# BV100011_ControlAI.net
KiCad netlist of a schematic drawn in Altium Designer
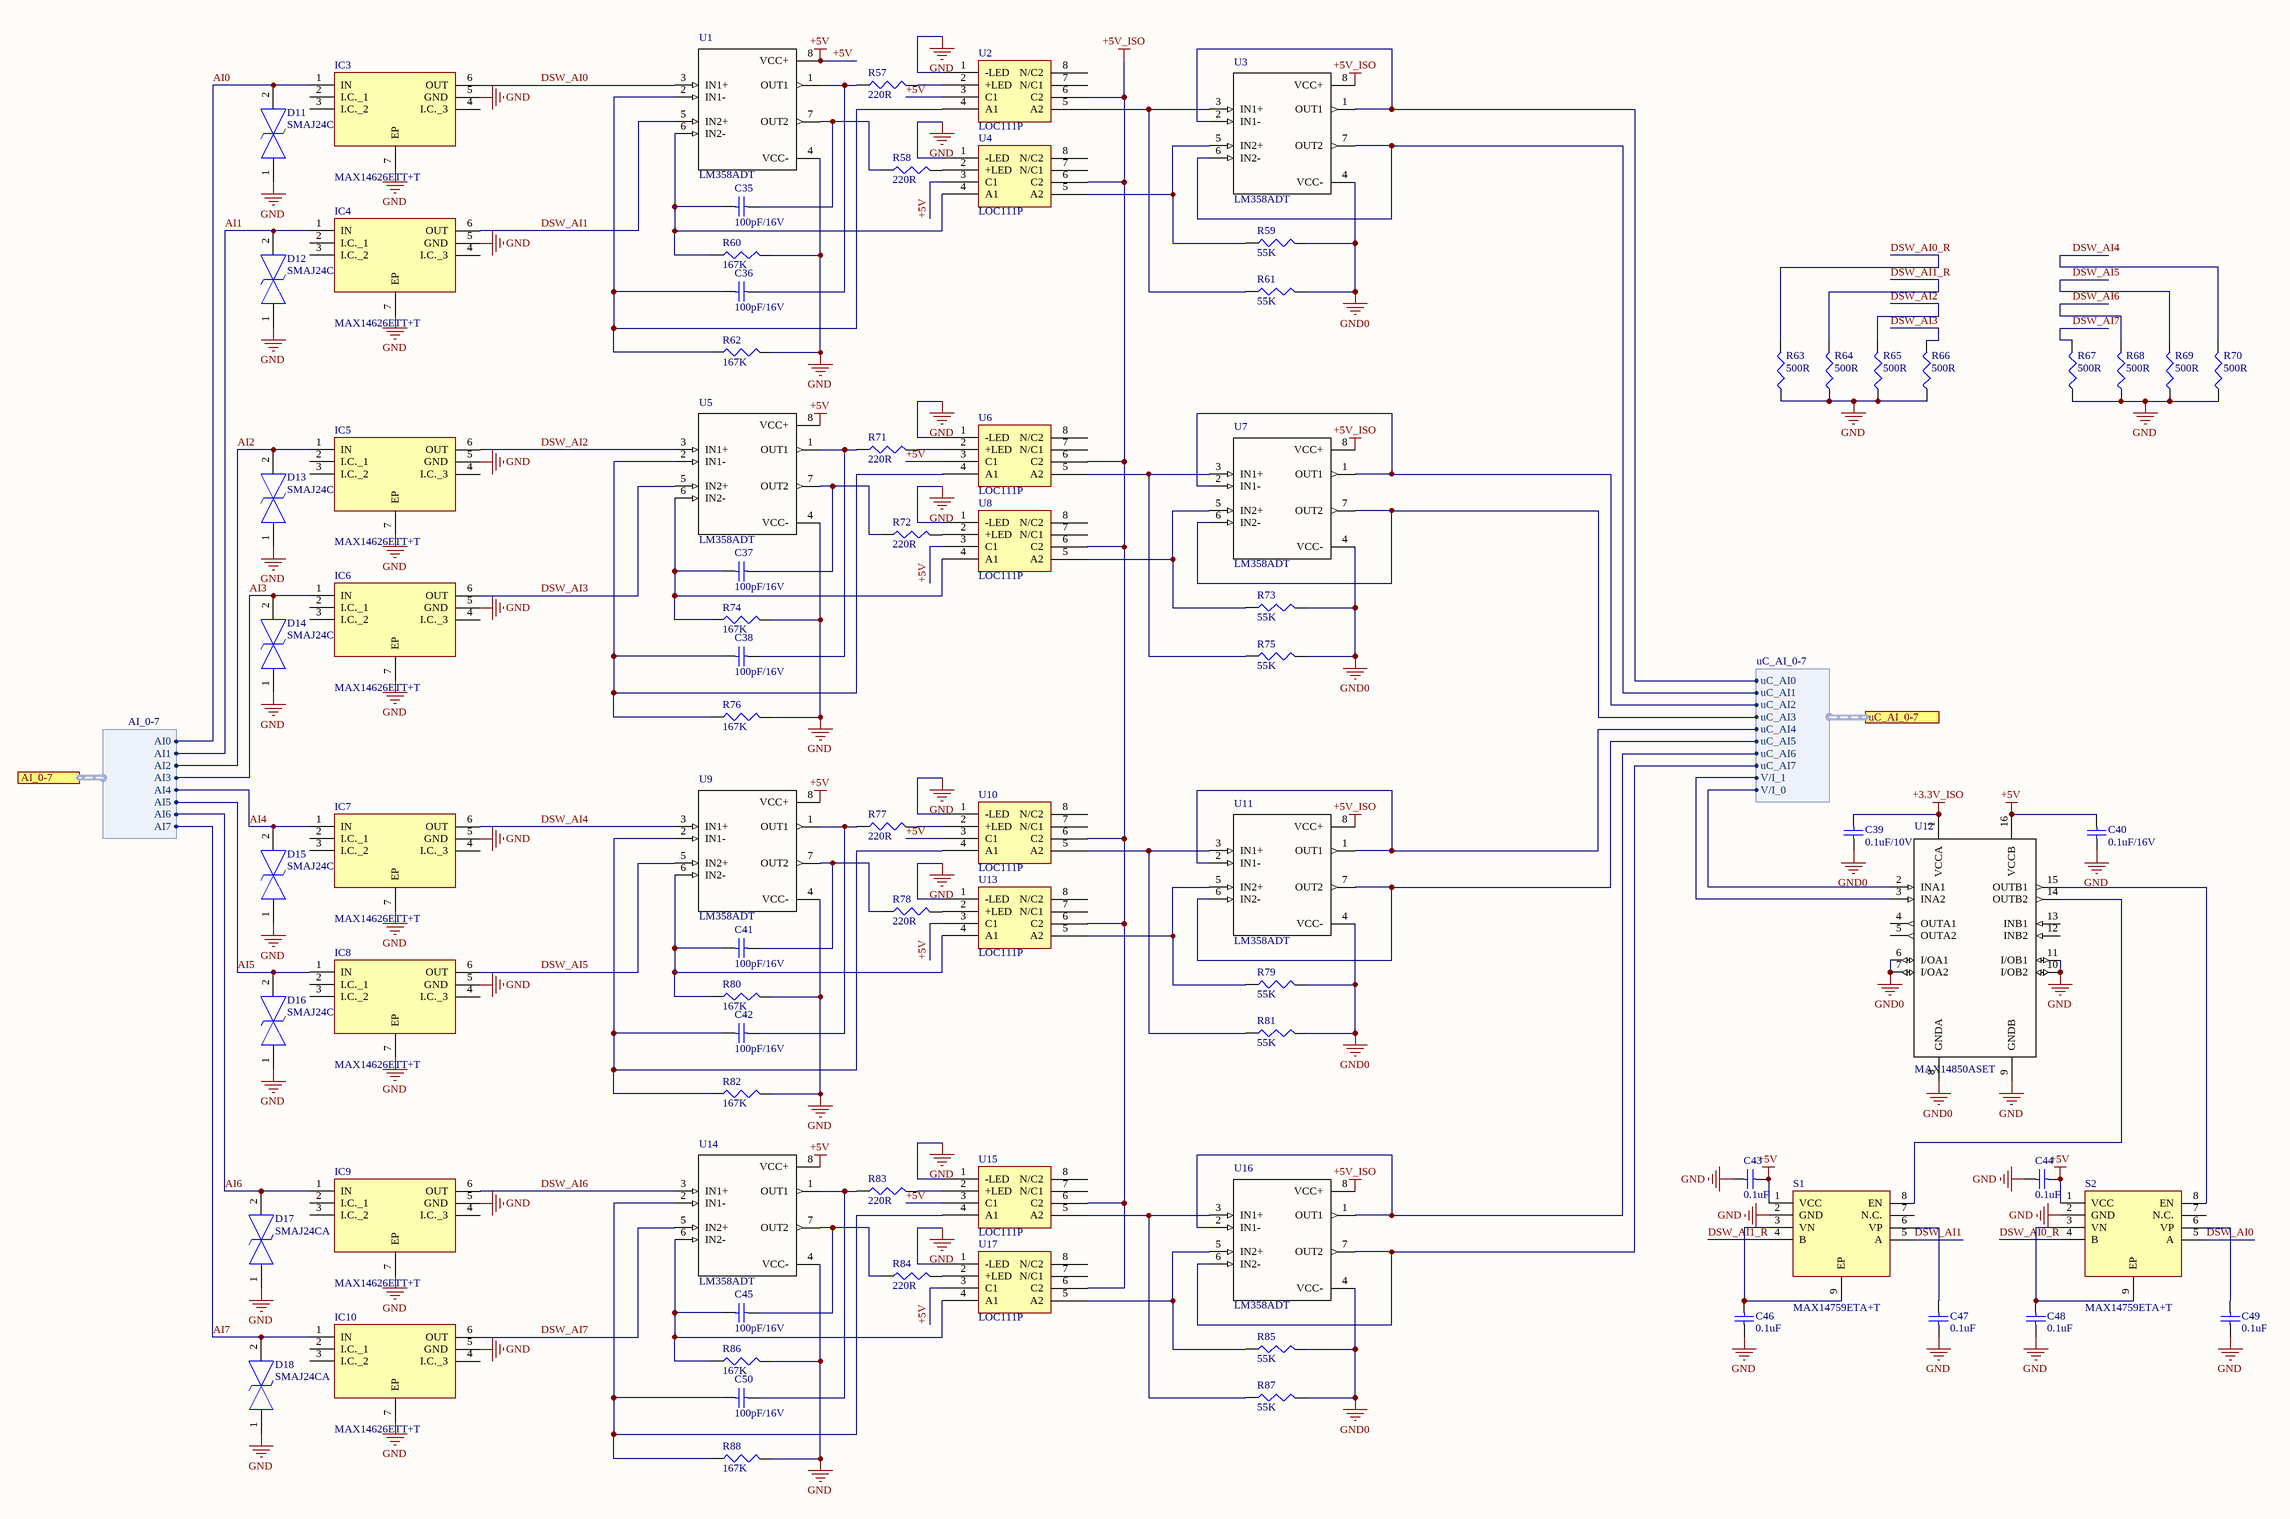
[diagram p0: BV100011_ControlAI.SchDoc]

(export (version "E")
  (design (tool "Eeschema 10.0.6"))
  (components
    (comp (ref "C35")
      (value "100pF/16V")
      (footprint "C1206")
      (description "Capacitor (Semiconductor SIM Model)")
      (fields (field (name "PUBLISHER") "Altium Limited"))
      (libsource (lib "Miscellaneous Devices") (part "Cap Semi"))
    )
    (comp (ref "C36")
      (value "100pF/16V")
      (footprint "C1206")
      (description "Capacitor (Semiconductor SIM Model)")
      (fields (field (name "PUBLISHER") "Altium Limited"))
      (libsource (lib "Miscellaneous Devices") (part "Cap Semi"))
    )
    (comp (ref "C37")
      (value "100pF/16V")
      (footprint "C1206")
      (description "Capacitor (Semiconductor SIM Model)")
      (fields (field (name "PUBLISHER") "Altium Limited"))
      (libsource (lib "Miscellaneous Devices") (part "Cap Semi"))
    )
    (comp (ref "C38")
      (value "100pF/16V")
      (footprint "C1206")
      (description "Capacitor (Semiconductor SIM Model)")
      (fields (field (name "PUBLISHER") "Altium Limited"))
      (libsource (lib "Miscellaneous Devices") (part "Cap Semi"))
    )
    (comp (ref "C39")
      (value "0.1uF/10V")
      (footprint "C1206")
      (description "Capacitor (Semiconductor SIM Model)")
      (fields (field (name "PUBLISHER") "Altium Limited"))
      (libsource (lib "Miscellaneous Devices") (part "Cap Semi"))
    )
    (comp (ref "C40")
      (value "0.1uF/16V")
      (footprint "C1206")
      (description "Capacitor (Semiconductor SIM Model)")
      (fields (field (name "PUBLISHER") "Altium Limited"))
      (libsource (lib "Miscellaneous Devices") (part "Cap Semi"))
    )
    (comp (ref "C41")
      (value "100pF/16V")
      (footprint "C1206")
      (description "Capacitor (Semiconductor SIM Model)")
      (fields (field (name "PUBLISHER") "Altium Limited"))
      (libsource (lib "Miscellaneous Devices") (part "Cap Semi"))
    )
    (comp (ref "C42")
      (value "100pF/16V")
      (footprint "C1206")
      (description "Capacitor (Semiconductor SIM Model)")
      (fields (field (name "PUBLISHER") "Altium Limited"))
      (libsource (lib "Miscellaneous Devices") (part "Cap Semi"))
    )
    (comp (ref "C43")
      (value "0.1uF")
      (footprint "C1206")
      (description "Capacitor (Semiconductor SIM Model)")
      (fields (field (name "PUBLISHER") "Altium Limited"))
      (libsource (lib "Miscellaneous Devices") (part "Cap Semi"))
    )
    (comp (ref "C44")
      (value "0.1uF")
      (footprint "C1206")
      (description "Capacitor (Semiconductor SIM Model)")
      (fields (field (name "PUBLISHER") "Altium Limited"))
      (libsource (lib "Miscellaneous Devices") (part "Cap Semi"))
    )
    (comp (ref "C45")
      (value "100pF/16V")
      (footprint "C1206")
      (description "Capacitor (Semiconductor SIM Model)")
      (fields (field (name "PUBLISHER") "Altium Limited"))
      (libsource (lib "Miscellaneous Devices") (part "Cap Semi"))
    )
    (comp (ref "C46")
      (value "0.1uF")
      (footprint "C1206")
      (description "Capacitor (Semiconductor SIM Model)")
      (fields (field (name "PUBLISHER") "Altium Limited"))
      (libsource (lib "Miscellaneous Devices") (part "Cap Semi"))
    )
    (comp (ref "C47")
      (value "0.1uF")
      (footprint "C1206")
      (description "Capacitor (Semiconductor SIM Model)")
      (fields (field (name "PUBLISHER") "Altium Limited"))
      (libsource (lib "Miscellaneous Devices") (part "Cap Semi"))
    )
    (comp (ref "C48")
      (value "0.1uF")
      (footprint "C1206")
      (description "Capacitor (Semiconductor SIM Model)")
      (fields (field (name "PUBLISHER") "Altium Limited"))
      (libsource (lib "Miscellaneous Devices") (part "Cap Semi"))
    )
    (comp (ref "C49")
      (value "0.1uF")
      (footprint "C1206")
      (description "Capacitor (Semiconductor SIM Model)")
      (fields (field (name "PUBLISHER") "Altium Limited"))
      (libsource (lib "Miscellaneous Devices") (part "Cap Semi"))
    )
    (comp (ref "C50")
      (value "100pF/16V")
      (footprint "C1206")
      (description "Capacitor (Semiconductor SIM Model)")
      (fields (field (name "PUBLISHER") "Altium Limited"))
      (libsource (lib "Miscellaneous Devices") (part "Cap Semi"))
    )
    (comp (ref "D11")
      (value "SMAJ24CA")
      (footprint "DIONM5026X229N")
      (description "TVS Diode (Bi-directional)")
      (fields (field (name "MOUSER PART NUMBER") "576-SMAJ24CA") (field (name "RS PART NUMBER") "1719613P"))
      (libsource (lib "SMAJ24CA") (part "SMAJ24CA"))
    )
    (comp (ref "D12")
      (value "SMAJ24CA")
      (footprint "DIONM5026X229N")
      (description "TVS Diode (Bi-directional)")
      (fields (field (name "MOUSER PART NUMBER") "576-SMAJ24CA") (field (name "RS PART NUMBER") "1719613P"))
      (libsource (lib "SMAJ24CA") (part "SMAJ24CA"))
    )
    (comp (ref "D13")
      (value "SMAJ24CA")
      (footprint "DIONM5026X229N")
      (description "TVS Diode (Bi-directional)")
      (fields (field (name "MOUSER PART NUMBER") "576-SMAJ24CA") (field (name "RS PART NUMBER") "1719613P"))
      (libsource (lib "SMAJ24CA") (part "SMAJ24CA"))
    )
    (comp (ref "D14")
      (value "SMAJ24CA")
      (footprint "DIONM5026X229N")
      (description "TVS Diode (Bi-directional)")
      (fields (field (name "MOUSER PART NUMBER") "576-SMAJ24CA") (field (name "RS PART NUMBER") "1719613P"))
      (libsource (lib "SMAJ24CA") (part "SMAJ24CA"))
    )
    (comp (ref "D15")
      (value "SMAJ24CA")
      (footprint "DIONM5026X229N")
      (description "TVS Diode (Bi-directional)")
      (fields (field (name "MOUSER PART NUMBER") "576-SMAJ24CA") (field (name "RS PART NUMBER") "1719613P"))
      (libsource (lib "SMAJ24CA") (part "SMAJ24CA"))
    )
    (comp (ref "D16")
      (value "SMAJ24CA")
      (footprint "DIONM5026X229N")
      (description "TVS Diode (Bi-directional)")
      (fields (field (name "MOUSER PART NUMBER") "576-SMAJ24CA") (field (name "RS PART NUMBER") "1719613P"))
      (libsource (lib "SMAJ24CA") (part "SMAJ24CA"))
    )
    (comp (ref "D17")
      (value "SMAJ24CA")
      (footprint "DIONM5026X229N")
      (description "TVS Diode (Bi-directional)")
      (fields (field (name "MOUSER PART NUMBER") "576-SMAJ24CA") (field (name "RS PART NUMBER") "1719613P"))
      (libsource (lib "SMAJ24CA") (part "SMAJ24CA"))
    )
    (comp (ref "D18")
      (value "SMAJ24CA")
      (footprint "DIONM5026X229N")
      (description "TVS Diode (Bi-directional)")
      (fields (field (name "MOUSER PART NUMBER") "576-SMAJ24CA") (field (name "RS PART NUMBER") "1719613P"))
      (libsource (lib "SMAJ24CA") (part "SMAJ24CA"))
    )
    (comp (ref "IC3")
      (value "MAX14626ETT+T")
      (footprint "SamacSys:SON95P300X300X80-7N")
      (description "Integrated Circuit")
      (fields (field (name "MOUSER PART NUMBER") "700-MAX14626ETT+T"))
      (libsource (lib "*") (part "MAX14626ETT+T"))
    )
    (comp (ref "IC4")
      (value "MAX14626ETT+T")
      (footprint "SamacSys:SON95P300X300X80-7N")
      (description "Integrated Circuit")
      (fields (field (name "MOUSER PART NUMBER") "700-MAX14626ETT+T"))
      (libsource (lib "*") (part "MAX14626ETT+T"))
    )
    (comp (ref "IC5")
      (value "MAX14626ETT+T")
      (footprint "SamacSys:SON95P300X300X80-7N")
      (description "Integrated Circuit")
      (fields (field (name "MOUSER PART NUMBER") "700-MAX14626ETT+T"))
      (libsource (lib "*") (part "MAX14626ETT+T"))
    )
    (comp (ref "IC6")
      (value "MAX14626ETT+T")
      (footprint "SamacSys:SON95P300X300X80-7N")
      (description "Integrated Circuit")
      (fields (field (name "MOUSER PART NUMBER") "700-MAX14626ETT+T"))
      (libsource (lib "*") (part "MAX14626ETT+T"))
    )
    (comp (ref "IC7")
      (value "MAX14626ETT+T")
      (footprint "SamacSys:SON95P300X300X80-7N")
      (description "Integrated Circuit")
      (fields (field (name "MOUSER PART NUMBER") "700-MAX14626ETT+T"))
      (libsource (lib "*") (part "MAX14626ETT+T"))
    )
    (comp (ref "IC8")
      (value "MAX14626ETT+T")
      (footprint "SamacSys:SON95P300X300X80-7N")
      (description "Integrated Circuit")
      (fields (field (name "MOUSER PART NUMBER") "700-MAX14626ETT+T"))
      (libsource (lib "*") (part "MAX14626ETT+T"))
    )
    (comp (ref "IC9")
      (value "MAX14626ETT+T")
      (footprint "SamacSys:SON95P300X300X80-7N")
      (description "Integrated Circuit")
      (fields (field (name "MOUSER PART NUMBER") "700-MAX14626ETT+T"))
      (libsource (lib "*") (part "MAX14626ETT+T"))
    )
    (comp (ref "IC10")
      (value "MAX14626ETT+T")
      (footprint "SamacSys:SON95P300X300X80-7N")
      (description "Integrated Circuit")
      (fields (field (name "MOUSER PART NUMBER") "700-MAX14626ETT+T"))
      (libsource (lib "*") (part "MAX14626ETT+T"))
    )
    (comp (ref "R57")
      (value "220R")
      (footprint "J1-0603")
      (description "Resistor")
      (fields (field (name "PUBLISHER") "Altium Limited"))
      (libsource (lib "Miscellaneous Devices") (part "Res3"))
    )
    (comp (ref "R58")
      (value "220R")
      (footprint "J1-0603")
      (description "Resistor")
      (fields (field (name "PUBLISHER") "Altium Limited"))
      (libsource (lib "Miscellaneous Devices") (part "Res3"))
    )
    (comp (ref "R59")
      (value "55K")
      (footprint "J1-0603")
      (description "Resistor")
      (fields (field (name "PUBLISHER") "Altium Limited"))
      (libsource (lib "Miscellaneous Devices") (part "Res3"))
    )
    (comp (ref "R60")
      (value "167K")
      (footprint "J1-0603")
      (description "Resistor")
      (fields (field (name "PUBLISHER") "Altium Limited"))
      (libsource (lib "Miscellaneous Devices") (part "Res3"))
    )
    (comp (ref "R61")
      (value "55K")
      (footprint "J1-0603")
      (description "Resistor")
      (fields (field (name "PUBLISHER") "Altium Limited"))
      (libsource (lib "Miscellaneous Devices") (part "Res3"))
    )
    (comp (ref "R62")
      (value "167K")
      (footprint "J1-0603")
      (description "Resistor")
      (fields (field (name "PUBLISHER") "Altium Limited"))
      (libsource (lib "Miscellaneous Devices") (part "Res3"))
    )
    (comp (ref "R63")
      (value "500R")
      (footprint "14-1210")
      (description "Resistor")
      (fields (field (name "PUBLISHER") "Altium Limited"))
      (libsource (lib "Miscellaneous Devices") (part "Res3"))
    )
    (comp (ref "R64")
      (value "500R")
      (footprint "14-1210")
      (description "Resistor")
      (fields (field (name "PUBLISHER") "Altium Limited"))
      (libsource (lib "Miscellaneous Devices") (part "Res3"))
    )
    (comp (ref "R65")
      (value "500R")
      (footprint "14-1210")
      (description "Resistor")
      (fields (field (name "PUBLISHER") "Altium Limited"))
      (libsource (lib "Miscellaneous Devices") (part "Res3"))
    )
    (comp (ref "R66")
      (value "500R")
      (footprint "14-1210")
      (description "Resistor")
      (fields (field (name "PUBLISHER") "Altium Limited"))
      (libsource (lib "Miscellaneous Devices") (part "Res3"))
    )
    (comp (ref "R67")
      (value "500R")
      (footprint "14-1210")
      (description "Resistor")
      (fields (field (name "PUBLISHER") "Altium Limited"))
      (libsource (lib "Miscellaneous Devices") (part "Res3"))
    )
    (comp (ref "R68")
      (value "500R")
      (footprint "14-1210")
      (description "Resistor")
      (fields (field (name "PUBLISHER") "Altium Limited"))
      (libsource (lib "Miscellaneous Devices") (part "Res3"))
    )
    (comp (ref "R69")
      (value "500R")
      (footprint "14-1210")
      (description "Resistor")
      (fields (field (name "PUBLISHER") "Altium Limited"))
      (libsource (lib "Miscellaneous Devices") (part "Res3"))
    )
    (comp (ref "R70")
      (value "500R")
      (footprint "14-1210")
      (description "Resistor")
      (fields (field (name "PUBLISHER") "Altium Limited"))
      (libsource (lib "Miscellaneous Devices") (part "Res3"))
    )
    (comp (ref "R71")
      (value "220R")
      (footprint "J1-0603")
      (description "Resistor")
      (fields (field (name "PUBLISHER") "Altium Limited"))
      (libsource (lib "Miscellaneous Devices") (part "Res3"))
    )
    (comp (ref "R72")
      (value "220R")
      (footprint "J1-0603")
      (description "Resistor")
      (fields (field (name "PUBLISHER") "Altium Limited"))
      (libsource (lib "Miscellaneous Devices") (part "Res3"))
    )
    (comp (ref "R73")
      (value "55K")
      (footprint "J1-0603")
      (description "Resistor")
      (fields (field (name "PUBLISHER") "Altium Limited"))
      (libsource (lib "Miscellaneous Devices") (part "Res3"))
    )
    (comp (ref "R74")
      (value "167K")
      (footprint "J1-0603")
      (description "Resistor")
      (fields (field (name "PUBLISHER") "Altium Limited"))
      (libsource (lib "Miscellaneous Devices") (part "Res3"))
    )
    (comp (ref "R75")
      (value "55K")
      (footprint "J1-0603")
      (description "Resistor")
      (fields (field (name "PUBLISHER") "Altium Limited"))
      (libsource (lib "Miscellaneous Devices") (part "Res3"))
    )
    (comp (ref "R76")
      (value "167K")
      (footprint "J1-0603")
      (description "Resistor")
      (fields (field (name "PUBLISHER") "Altium Limited"))
      (libsource (lib "Miscellaneous Devices") (part "Res3"))
    )
    (comp (ref "R77")
      (value "220R")
      (footprint "J1-0603")
      (description "Resistor")
      (fields (field (name "PUBLISHER") "Altium Limited"))
      (libsource (lib "Miscellaneous Devices") (part "Res3"))
    )
    (comp (ref "R78")
      (value "220R")
      (footprint "J1-0603")
      (description "Resistor")
      (fields (field (name "PUBLISHER") "Altium Limited"))
      (libsource (lib "Miscellaneous Devices") (part "Res3"))
    )
    (comp (ref "R79")
      (value "55K")
      (footprint "J1-0603")
      (description "Resistor")
      (fields (field (name "PUBLISHER") "Altium Limited"))
      (libsource (lib "Miscellaneous Devices") (part "Res3"))
    )
    (comp (ref "R80")
      (value "167K")
      (footprint "J1-0603")
      (description "Resistor")
      (fields (field (name "PUBLISHER") "Altium Limited"))
      (libsource (lib "Miscellaneous Devices") (part "Res3"))
    )
    (comp (ref "R81")
      (value "55K")
      (footprint "J1-0603")
      (description "Resistor")
      (fields (field (name "PUBLISHER") "Altium Limited"))
      (libsource (lib "Miscellaneous Devices") (part "Res3"))
    )
    (comp (ref "R82")
      (value "167K")
      (footprint "J1-0603")
      (description "Resistor")
      (fields (field (name "PUBLISHER") "Altium Limited"))
      (libsource (lib "Miscellaneous Devices") (part "Res3"))
    )
    (comp (ref "R83")
      (value "220R")
      (footprint "J1-0603")
      (description "Resistor")
      (fields (field (name "PUBLISHER") "Altium Limited"))
      (libsource (lib "Miscellaneous Devices") (part "Res3"))
    )
    (comp (ref "R84")
      (value "220R")
      (footprint "J1-0603")
      (description "Resistor")
      (fields (field (name "PUBLISHER") "Altium Limited"))
      (libsource (lib "Miscellaneous Devices") (part "Res3"))
    )
    (comp (ref "R85")
      (value "55K")
      (footprint "J1-0603")
      (description "Resistor")
      (fields (field (name "PUBLISHER") "Altium Limited"))
      (libsource (lib "Miscellaneous Devices") (part "Res3"))
    )
    (comp (ref "R86")
      (value "167K")
      (footprint "J1-0603")
      (description "Resistor")
      (fields (field (name "PUBLISHER") "Altium Limited"))
      (libsource (lib "Miscellaneous Devices") (part "Res3"))
    )
    (comp (ref "R87")
      (value "55K")
      (footprint "J1-0603")
      (description "Resistor")
      (fields (field (name "PUBLISHER") "Altium Limited"))
      (libsource (lib "Miscellaneous Devices") (part "Res3"))
    )
    (comp (ref "R88")
      (value "167K")
      (footprint "J1-0603")
      (description "Resistor")
      (fields (field (name "PUBLISHER") "Altium Limited"))
      (libsource (lib "Miscellaneous Devices") (part "Res3"))
    )
    (comp (ref "S1")
      (value "MAX14759ETA+T")
      (footprint "SamacSys:SON65P300X300X80-9N")
      (description "Switch")
      (fields (field (name "MOUSER PART NUMBER") "700-MAX14759ETA+T"))
      (libsource (lib "*") (part "MAX14759ETA+T"))
    )
    (comp (ref "S2")
      (value "MAX14759ETA+T")
      (footprint "SamacSys:SON65P300X300X80-9N")
      (description "Switch")
      (fields (field (name "MOUSER PART NUMBER") "700-MAX14759ETA+T"))
      (libsource (lib "*") (part "MAX14759ETA+T"))
    )
    (comp (ref "U1")
      (value "LM358ADT")
      (footprint "*SOIC127P600X175-8N")
      (description "LM358 Series 30 V 1.1 MHz Low Power Dual Operational Amplifier - SOIC-8")
      (fields (field (name "MF") "STMicroelectronics"))
      (libsource (lib "LM358ADT") (part "LM358ADT"))
    )
    (comp (ref "U2")
      (value "LOC111P")
      (footprint "SOP254P940X265-8N")
      (description "Linear Optocoupler")
      (libsource (lib "LOC111P") (part "LOC111P"))
    )
    (comp (ref "U3")
      (value "LM358ADT")
      (footprint "*SOIC127P600X175-8N")
      (description "LM358 Series 30 V 1.1 MHz Low Power Dual Operational Amplifier - SOIC-8")
      (fields (field (name "MF") "STMicroelectronics"))
      (libsource (lib "LM358ADT") (part "LM358ADT"))
    )
    (comp (ref "U4")
      (value "LOC111P")
      (footprint "SOP254P940X265-8N")
      (description "Linear Optocoupler")
      (libsource (lib "LOC111P") (part "LOC111P"))
    )
    (comp (ref "U5")
      (value "LM358ADT")
      (footprint "*SOIC127P600X175-8N")
      (description "LM358 Series 30 V 1.1 MHz Low Power Dual Operational Amplifier - SOIC-8")
      (fields (field (name "MF") "STMicroelectronics"))
      (libsource (lib "LM358ADT") (part "LM358ADT"))
    )
    (comp (ref "U6")
      (value "LOC111P")
      (footprint "SOP254P940X265-8N")
      (description "Linear Optocoupler")
      (libsource (lib "LOC111P") (part "LOC111P"))
    )
    (comp (ref "U7")
      (value "LM358ADT")
      (footprint "*SOIC127P600X175-8N")
      (description "LM358 Series 30 V 1.1 MHz Low Power Dual Operational Amplifier - SOIC-8")
      (fields (field (name "MF") "STMicroelectronics"))
      (libsource (lib "LM358ADT") (part "LM358ADT"))
    )
    (comp (ref "U8")
      (value "LOC111P")
      (footprint "SOP254P940X265-8N")
      (description "Linear Optocoupler")
      (libsource (lib "LOC111P") (part "LOC111P"))
    )
    (comp (ref "U9")
      (value "LM358ADT")
      (footprint "*SOIC127P600X175-8N")
      (description "LM358 Series 30 V 1.1 MHz Low Power Dual Operational Amplifier - SOIC-8")
      (fields (field (name "MF") "STMicroelectronics"))
      (libsource (lib "LM358ADT") (part "LM358ADT"))
    )
    (comp (ref "U10")
      (value "LOC111P")
      (footprint "SOP254P940X265-8N")
      (description "Linear Optocoupler")
      (libsource (lib "LOC111P") (part "LOC111P"))
    )
    (comp (ref "U11")
      (value "LM358ADT")
      (footprint "*SOIC127P600X175-8N")
      (description "LM358 Series 30 V 1.1 MHz Low Power Dual Operational Amplifier - SOIC-8")
      (fields (field (name "MF") "STMicroelectronics"))
      (libsource (lib "LM358ADT") (part "LM358ADT"))
    )
    (comp (ref "U12")
      (value "MAX14850ASET")
      (footprint "*SOIC127P600X175-16N")
      (description "Digital Isolator, 6-Ch, 30ns, Nsoic-16")
      (fields (field (name "MF") "Maxim Integrated") (field (name "MP") "MAX14850ASE+"))
      (libsource (lib "MAX14850ASET") (part "MAX14850ASET"))
    )
    (comp (ref "U13")
      (value "LOC111P")
      (footprint "SOP254P940X265-8N")
      (description "Linear Optocoupler")
      (libsource (lib "LOC111P") (part "LOC111P"))
    )
    (comp (ref "U14")
      (value "LM358ADT")
      (footprint "*SOIC127P600X175-8N")
      (description "LM358 Series 30 V 1.1 MHz Low Power Dual Operational Amplifier - SOIC-8")
      (fields (field (name "MF") "STMicroelectronics"))
      (libsource (lib "LM358ADT") (part "LM358ADT"))
    )
    (comp (ref "U15")
      (value "LOC111P")
      (footprint "SOP254P940X265-8N")
      (description "Linear Optocoupler")
      (libsource (lib "LOC111P") (part "LOC111P"))
    )
    (comp (ref "U16")
      (value "LM358ADT")
      (footprint "*SOIC127P600X175-8N")
      (description "LM358 Series 30 V 1.1 MHz Low Power Dual Operational Amplifier - SOIC-8")
      (fields (field (name "MF") "STMicroelectronics"))
      (libsource (lib "LM358ADT") (part "LM358ADT"))
    )
    (comp (ref "U17")
      (value "LOC111P")
      (footprint "SOP254P940X265-8N")
      (description "Linear Optocoupler")
      (libsource (lib "LOC111P") (part "LOC111P"))
    )
  )
  (nets
    (net (code "3") (name "+3.3V_ISO") (class "Default")
      (node (ref "C39") (pin "1") (pinfunction "1_1") (pintype "passive"))
      (node (ref "U12") (pin "1") (pinfunction "VCCA_1") (pintype "power_in"))
    )
    (net (code "4") (name "+5V") (class "Default")
      (node (ref "C40") (pin "1") (pinfunction "1_1") (pintype "passive"))
      (node (ref "C43") (pin "2") (pinfunction "2_2") (pintype "passive"))
      (node (ref "C44") (pin "2") (pinfunction "2_2") (pintype "passive"))
      (node (ref "S1") (pin "1") (pinfunction "VCC_1") (pintype "power_in"))
      (node (ref "S2") (pin "1") (pinfunction "VCC_1") (pintype "power_in"))
      (node (ref "U1") (pin "8") (pinfunction "VCC+_8") (pintype "power_in"))
      (node (ref "U10") (pin "3") (pinfunction "C1_3") (pintype "passive"))
      (node (ref "U12") (pin "16") (pinfunction "VCCB_16") (pintype "power_in"))
      (node (ref "U13") (pin "3") (pinfunction "C1_3") (pintype "passive"))
      (node (ref "U14") (pin "8") (pinfunction "VCC+_8") (pintype "power_in"))
      (node (ref "U15") (pin "3") (pinfunction "C1_3") (pintype "passive"))
      (node (ref "U17") (pin "3") (pinfunction "C1_3") (pintype "passive"))
      (node (ref "U2") (pin "3") (pinfunction "C1_3") (pintype "passive"))
      (node (ref "U4") (pin "3") (pinfunction "C1_3") (pintype "passive"))
      (node (ref "U5") (pin "8") (pinfunction "VCC+_8") (pintype "power_in"))
      (node (ref "U6") (pin "3") (pinfunction "C1_3") (pintype "passive"))
      (node (ref "U8") (pin "3") (pinfunction "C1_3") (pintype "passive"))
      (node (ref "U9") (pin "8") (pinfunction "VCC+_8") (pintype "power_in"))
    )
    (net (code "5") (name "+5V_ISO") (class "Default")
      (node (ref "U10") (pin "6") (pinfunction "C2_6") (pintype "passive"))
      (node (ref "U11") (pin "8") (pinfunction "VCC+_8") (pintype "power_in"))
      (node (ref "U13") (pin "6") (pinfunction "C2_6") (pintype "passive"))
      (node (ref "U15") (pin "6") (pinfunction "C2_6") (pintype "passive"))
      (node (ref "U16") (pin "8") (pinfunction "VCC+_8") (pintype "power_in"))
      (node (ref "U17") (pin "6") (pinfunction "C2_6") (pintype "passive"))
      (node (ref "U2") (pin "6") (pinfunction "C2_6") (pintype "passive"))
      (node (ref "U3") (pin "8") (pinfunction "VCC+_8") (pintype "power_in"))
      (node (ref "U4") (pin "6") (pinfunction "C2_6") (pintype "passive"))
      (node (ref "U6") (pin "6") (pinfunction "C2_6") (pintype "passive"))
      (node (ref "U7") (pin "8") (pinfunction "VCC+_8") (pintype "power_in"))
      (node (ref "U8") (pin "6") (pinfunction "C2_6") (pintype "passive"))
    )
    (net (code "6") (name "/AI0") (class "Default")
      (node (ref "D11") (pin "2") (pinfunction "A_2") (pintype "passive"))
      (node (ref "IC3") (pin "1") (pinfunction "IN_1") (pintype "passive"))
    )
    (net (code "7") (name "/AI1") (class "Default")
      (node (ref "D12") (pin "2") (pinfunction "A_2") (pintype "passive"))
      (node (ref "IC4") (pin "1") (pinfunction "IN_1") (pintype "passive"))
    )
    (net (code "8") (name "/AI2") (class "Default")
      (node (ref "D13") (pin "2") (pinfunction "A_2") (pintype "passive"))
      (node (ref "IC5") (pin "1") (pinfunction "IN_1") (pintype "passive"))
    )
    (net (code "9") (name "/AI3") (class "Default")
      (node (ref "D14") (pin "2") (pinfunction "A_2") (pintype "passive"))
      (node (ref "IC6") (pin "1") (pinfunction "IN_1") (pintype "passive"))
    )
    (net (code "10") (name "/AI4") (class "Default")
      (node (ref "D15") (pin "2") (pinfunction "A_2") (pintype "passive"))
      (node (ref "IC7") (pin "1") (pinfunction "IN_1") (pintype "passive"))
    )
    (net (code "11") (name "/AI5") (class "Default")
      (node (ref "D16") (pin "2") (pinfunction "A_2") (pintype "passive"))
      (node (ref "IC8") (pin "1") (pinfunction "IN_1") (pintype "passive"))
    )
    (net (code "12") (name "/AI6") (class "Default")
      (node (ref "D17") (pin "2") (pinfunction "A_2") (pintype "passive"))
      (node (ref "IC9") (pin "1") (pinfunction "IN_1") (pintype "passive"))
    )
    (net (code "13") (name "/AI7") (class "Default")
      (node (ref "D18") (pin "2") (pinfunction "A_2") (pintype "passive"))
      (node (ref "IC10") (pin "1") (pinfunction "IN_1") (pintype "passive"))
    )
    (net (code "14") (name "/DSW_AI0") (class "Default")
      (node (ref "IC3") (pin "6") (pinfunction "OUT_6") (pintype "passive"))
      (node (ref "S2") (pin "5") (pinfunction "A_5") (pintype "passive"))
      (node (ref "U1") (pin "3") (pinfunction "IN1+_3") (pintype "input"))
    )
    (net (code "15") (name "/DSW_AI0_R") (class "Default")
      (node (ref "R63") (pin "2") (pinfunction "2_2") (pintype "passive"))
      (node (ref "S2") (pin "4") (pinfunction "B_4") (pintype "passive"))
    )
    (net (code "16") (name "/DSW_AI1") (class "Default")
      (node (ref "IC4") (pin "6") (pinfunction "OUT_6") (pintype "passive"))
      (node (ref "S1") (pin "5") (pinfunction "A_5") (pintype "passive"))
      (node (ref "U1") (pin "5") (pinfunction "IN2+_5") (pintype "input"))
    )
    (net (code "17") (name "/DSW_AI1_R") (class "Default")
      (node (ref "R64") (pin "2") (pinfunction "2_2") (pintype "passive"))
      (node (ref "S1") (pin "4") (pinfunction "B_4") (pintype "passive"))
    )
    (net (code "18") (name "/DSW_AI2") (class "Default")
      (node (ref "IC5") (pin "6") (pinfunction "OUT_6") (pintype "passive"))
      (node (ref "R65") (pin "2") (pinfunction "2_2") (pintype "passive"))
      (node (ref "U5") (pin "3") (pinfunction "IN1+_3") (pintype "input"))
    )
    (net (code "19") (name "/DSW_AI3") (class "Default")
      (node (ref "IC6") (pin "6") (pinfunction "OUT_6") (pintype "passive"))
      (node (ref "R66") (pin "2") (pinfunction "2_2") (pintype "passive"))
      (node (ref "U5") (pin "5") (pinfunction "IN2+_5") (pintype "input"))
    )
    (net (code "20") (name "/DSW_AI4") (class "Default")
      (node (ref "IC7") (pin "6") (pinfunction "OUT_6") (pintype "passive"))
      (node (ref "R70") (pin "2") (pinfunction "2_2") (pintype "passive"))
      (node (ref "U9") (pin "3") (pinfunction "IN1+_3") (pintype "input"))
    )
    (net (code "21") (name "/DSW_AI5") (class "Default")
      (node (ref "IC8") (pin "6") (pinfunction "OUT_6") (pintype "passive"))
      (node (ref "R69") (pin "2") (pinfunction "2_2") (pintype "passive"))
      (node (ref "U9") (pin "5") (pinfunction "IN2+_5") (pintype "input"))
    )
    (net (code "22") (name "/DSW_AI6") (class "Default")
      (node (ref "IC9") (pin "6") (pinfunction "OUT_6") (pintype "passive"))
      (node (ref "R68") (pin "2") (pinfunction "2_2") (pintype "passive"))
      (node (ref "U14") (pin "3") (pinfunction "IN1+_3") (pintype "input"))
    )
    (net (code "23") (name "/DSW_AI7") (class "Default")
      (node (ref "IC10") (pin "6") (pinfunction "OUT_6") (pintype "passive"))
      (node (ref "R67") (pin "2") (pinfunction "2_2") (pintype "passive"))
      (node (ref "U14") (pin "5") (pinfunction "IN2+_5") (pintype "input"))
    )
    (net (code "24") (name "/V{slash}I_0") (class "Default")
      (node (ref "U12") (pin "2") (pinfunction "INA1_2") (pintype "input"))
    )
    (net (code "25") (name "/V{slash}I_1") (class "Default")
      (node (ref "U12") (pin "3") (pinfunction "INA2_3") (pintype "input"))
    )
    (net (code "26") (name "/uC_AI0") (class "Default")
      (node (ref "U3") (pin "1") (pinfunction "OUT1_1") (pintype "output"))
      (node (ref "U3") (pin "2") (pinfunction "IN1-_2") (pintype "input"))
    )
    (net (code "27") (name "/uC_AI1") (class "Default")
      (node (ref "U3") (pin "6") (pinfunction "IN2-_6") (pintype "input"))
      (node (ref "U3") (pin "7") (pinfunction "OUT2_7") (pintype "output"))
    )
    (net (code "28") (name "/uC_AI2") (class "Default")
      (node (ref "U7") (pin "1") (pinfunction "OUT1_1") (pintype "output"))
      (node (ref "U7") (pin "2") (pinfunction "IN1-_2") (pintype "input"))
    )
    (net (code "29") (name "/uC_AI3") (class "Default")
      (node (ref "U7") (pin "6") (pinfunction "IN2-_6") (pintype "input"))
      (node (ref "U7") (pin "7") (pinfunction "OUT2_7") (pintype "output"))
    )
    (net (code "30") (name "/uC_AI4") (class "Default")
      (node (ref "U11") (pin "1") (pinfunction "OUT1_1") (pintype "output"))
      (node (ref "U11") (pin "2") (pinfunction "IN1-_2") (pintype "input"))
    )
    (net (code "31") (name "/uC_AI5") (class "Default")
      (node (ref "U11") (pin "6") (pinfunction "IN2-_6") (pintype "input"))
      (node (ref "U11") (pin "7") (pinfunction "OUT2_7") (pintype "output"))
    )
    (net (code "32") (name "/uC_AI6") (class "Default")
      (node (ref "U16") (pin "1") (pinfunction "OUT1_1") (pintype "output"))
      (node (ref "U16") (pin "2") (pinfunction "IN1-_2") (pintype "input"))
    )
    (net (code "33") (name "/uC_AI7") (class "Default")
      (node (ref "U16") (pin "6") (pinfunction "IN2-_6") (pintype "input"))
      (node (ref "U16") (pin "7") (pinfunction "OUT2_7") (pintype "output"))
    )
    (net (code "36") (name "GND") (class "Default")
      (node (ref "C40") (pin "2") (pinfunction "2_2") (pintype "passive"))
      (node (ref "C43") (pin "1") (pinfunction "1_1") (pintype "passive"))
      (node (ref "C44") (pin "1") (pinfunction "1_1") (pintype "passive"))
      (node (ref "C46") (pin "2") (pinfunction "2_2") (pintype "passive"))
      (node (ref "C47") (pin "2") (pinfunction "2_2") (pintype "passive"))
      (node (ref "C48") (pin "2") (pinfunction "2_2") (pintype "passive"))
      (node (ref "C49") (pin "2") (pinfunction "2_2") (pintype "passive"))
      (node (ref "D11") (pin "1") (pinfunction "K_1") (pintype "passive"))
      (node (ref "D12") (pin "1") (pinfunction "K_1") (pintype "passive"))
      (node (ref "D13") (pin "1") (pinfunction "K_1") (pintype "passive"))
      (node (ref "D14") (pin "1") (pinfunction "K_1") (pintype "passive"))
      (node (ref "D15") (pin "1") (pinfunction "K_1") (pintype "passive"))
      (node (ref "D16") (pin "1") (pinfunction "K_1") (pintype "passive"))
      (node (ref "D17") (pin "1") (pinfunction "K_1") (pintype "passive"))
      (node (ref "D18") (pin "1") (pinfunction "K_1") (pintype "passive"))
      (node (ref "IC10") (pin "5") (pinfunction "GND_5") (pintype "passive"))
      (node (ref "IC10") (pin "7") (pinfunction "EP_7") (pintype "passive"))
      (node (ref "IC3") (pin "5") (pinfunction "GND_5") (pintype "passive"))
      (node (ref "IC3") (pin "7") (pinfunction "EP_7") (pintype "passive"))
      (node (ref "IC4") (pin "5") (pinfunction "GND_5") (pintype "passive"))
      (node (ref "IC4") (pin "7") (pinfunction "EP_7") (pintype "passive"))
      (node (ref "IC5") (pin "5") (pinfunction "GND_5") (pintype "passive"))
      (node (ref "IC5") (pin "7") (pinfunction "EP_7") (pintype "passive"))
      (node (ref "IC6") (pin "5") (pinfunction "GND_5") (pintype "passive"))
      (node (ref "IC6") (pin "7") (pinfunction "EP_7") (pintype "passive"))
      (node (ref "IC7") (pin "5") (pinfunction "GND_5") (pintype "passive"))
      (node (ref "IC7") (pin "7") (pinfunction "EP_7") (pintype "passive"))
      (node (ref "IC8") (pin "5") (pinfunction "GND_5") (pintype "passive"))
      (node (ref "IC8") (pin "7") (pinfunction "EP_7") (pintype "passive"))
      (node (ref "IC9") (pin "5") (pinfunction "GND_5") (pintype "passive"))
      (node (ref "IC9") (pin "7") (pinfunction "EP_7") (pintype "passive"))
      (node (ref "R60") (pin "2") (pinfunction "2_2") (pintype "passive"))
      (node (ref "R62") (pin "2") (pinfunction "2_2") (pintype "passive"))
      (node (ref "R63") (pin "1") (pinfunction "1_1") (pintype "passive"))
      (node (ref "R64") (pin "1") (pinfunction "1_1") (pintype "passive"))
      (node (ref "R65") (pin "1") (pinfunction "1_1") (pintype "passive"))
      (node (ref "R66") (pin "1") (pinfunction "1_1") (pintype "passive"))
      (node (ref "R67") (pin "1") (pinfunction "1_1") (pintype "passive"))
      (node (ref "R68") (pin "1") (pinfunction "1_1") (pintype "passive"))
      (node (ref "R69") (pin "1") (pinfunction "1_1") (pintype "passive"))
      (node (ref "R70") (pin "1") (pinfunction "1_1") (pintype "passive"))
      (node (ref "R74") (pin "2") (pinfunction "2_2") (pintype "passive"))
      (node (ref "R76") (pin "2") (pinfunction "2_2") (pintype "passive"))
      (node (ref "R80") (pin "2") (pinfunction "2_2") (pintype "passive"))
      (node (ref "R82") (pin "2") (pinfunction "2_2") (pintype "passive"))
      (node (ref "R86") (pin "2") (pinfunction "2_2") (pintype "passive"))
      (node (ref "R88") (pin "2") (pinfunction "2_2") (pintype "passive"))
      (node (ref "S1") (pin "2") (pinfunction "GND_2") (pintype "power_in"))
      (node (ref "S2") (pin "2") (pinfunction "GND_2") (pintype "power_in"))
      (node (ref "U1") (pin "4") (pinfunction "VCC-_4") (pintype "power_in"))
      (node (ref "U10") (pin "1") (pinfunction "-LED_1") (pintype "passive"))
      (node (ref "U12") (pin "10") (pinfunction "I/OB2_10") (pintype "bidirectional"))
      (node (ref "U12") (pin "11") (pinfunction "I/OB1_11") (pintype "bidirectional"))
      (node (ref "U12") (pin "9") (pinfunction "GNDB_9") (pintype "power_in"))
      (node (ref "U13") (pin "1") (pinfunction "-LED_1") (pintype "passive"))
      (node (ref "U14") (pin "4") (pinfunction "VCC-_4") (pintype "power_in"))
      (node (ref "U15") (pin "1") (pinfunction "-LED_1") (pintype "passive"))
      (node (ref "U17") (pin "1") (pinfunction "-LED_1") (pintype "passive"))
      (node (ref "U2") (pin "1") (pinfunction "-LED_1") (pintype "passive"))
      (node (ref "U4") (pin "1") (pinfunction "-LED_1") (pintype "passive"))
      (node (ref "U5") (pin "4") (pinfunction "VCC-_4") (pintype "power_in"))
      (node (ref "U6") (pin "1") (pinfunction "-LED_1") (pintype "passive"))
      (node (ref "U8") (pin "1") (pinfunction "-LED_1") (pintype "passive"))
      (node (ref "U9") (pin "4") (pinfunction "VCC-_4") (pintype "power_in"))
    )
    (net (code "37") (name "GND0") (class "Default")
      (node (ref "C39") (pin "2") (pinfunction "2_2") (pintype "passive"))
      (node (ref "R59") (pin "2") (pinfunction "2_2") (pintype "passive"))
      (node (ref "R61") (pin "2") (pinfunction "2_2") (pintype "passive"))
      (node (ref "R73") (pin "2") (pinfunction "2_2") (pintype "passive"))
      (node (ref "R75") (pin "2") (pinfunction "2_2") (pintype "passive"))
      (node (ref "R79") (pin "2") (pinfunction "2_2") (pintype "passive"))
      (node (ref "R81") (pin "2") (pinfunction "2_2") (pintype "passive"))
      (node (ref "R85") (pin "2") (pinfunction "2_2") (pintype "passive"))
      (node (ref "R87") (pin "2") (pinfunction "2_2") (pintype "passive"))
      (node (ref "U11") (pin "4") (pinfunction "VCC-_4") (pintype "power_in"))
      (node (ref "U12") (pin "6") (pinfunction "I/OA1_6") (pintype "bidirectional"))
      (node (ref "U12") (pin "7") (pinfunction "I/OA2_7") (pintype "bidirectional"))
      (node (ref "U12") (pin "8") (pinfunction "GNDA_8") (pintype "power_in"))
      (node (ref "U16") (pin "4") (pinfunction "VCC-_4") (pintype "power_in"))
      (node (ref "U3") (pin "4") (pinfunction "VCC-_4") (pintype "power_in"))
      (node (ref "U7") (pin "4") (pinfunction "VCC-_4") (pintype "power_in"))
    )
    (net (code "38") (name "Net-(S1-EN)") (class "Default")
      (node (ref "S1") (pin "8") (pinfunction "EN_8") (pintype "passive"))
      (node (ref "U12") (pin "14") (pinfunction "OUTB2_14") (pintype "output"))
    )
    (net (code "39") (name "Net-(S1-EP)") (class "Default")
      (node (ref "C46") (pin "1") (pinfunction "1_1") (pintype "passive"))
      (node (ref "S1") (pin "3") (pinfunction "VN_3") (pintype "passive"))
      (node (ref "S1") (pin "9") (pinfunction "EP_9") (pintype "passive"))
    )
    (net (code "40") (name "Net-(S1-VP)") (class "Default")
      (node (ref "C47") (pin "1") (pinfunction "1_1") (pintype "passive"))
      (node (ref "S1") (pin "6") (pinfunction "VP_6") (pintype "passive"))
    )
    (net (code "41") (name "Net-(S2-EN)") (class "Default")
      (node (ref "S2") (pin "8") (pinfunction "EN_8") (pintype "passive"))
      (node (ref "U12") (pin "15") (pinfunction "OUTB1_15") (pintype "output"))
    )
    (net (code "42") (name "Net-(S2-EP)") (class "Default")
      (node (ref "C48") (pin "1") (pinfunction "1_1") (pintype "passive"))
      (node (ref "S2") (pin "3") (pinfunction "VN_3") (pintype "passive"))
      (node (ref "S2") (pin "9") (pinfunction "EP_9") (pintype "passive"))
    )
    (net (code "43") (name "Net-(S2-VP)") (class "Default")
      (node (ref "C49") (pin "1") (pinfunction "1_1") (pintype "passive"))
      (node (ref "S2") (pin "6") (pinfunction "VP_6") (pintype "passive"))
    )
    (net (code "44") (name "Net-(U1-IN1-)") (class "Default")
      (node (ref "C36") (pin "1") (pinfunction "1_1") (pintype "passive"))
      (node (ref "R62") (pin "1") (pinfunction "1_1") (pintype "passive"))
      (node (ref "U1") (pin "2") (pinfunction "IN1-_2") (pintype "input"))
      (node (ref "U2") (pin "4") (pinfunction "A1_4") (pintype "passive"))
    )
    (net (code "45") (name "Net-(U1-IN2-)") (class "Default")
      (node (ref "C35") (pin "1") (pinfunction "1_1") (pintype "passive"))
      (node (ref "R60") (pin "1") (pinfunction "1_1") (pintype "passive"))
      (node (ref "U1") (pin "6") (pinfunction "IN2-_6") (pintype "input"))
      (node (ref "U4") (pin "4") (pinfunction "A1_4") (pintype "passive"))
    )
    (net (code "46") (name "Net-(U1-OUT1)") (class "Default")
      (node (ref "C36") (pin "2") (pinfunction "2_2") (pintype "passive"))
      (node (ref "R57") (pin "1") (pinfunction "1_1") (pintype "passive"))
      (node (ref "U1") (pin "1") (pinfunction "OUT1_1") (pintype "output"))
    )
    (net (code "47") (name "Net-(U1-OUT2)") (class "Default")
      (node (ref "C35") (pin "2") (pinfunction "2_2") (pintype "passive"))
      (node (ref "R58") (pin "1") (pinfunction "1_1") (pintype "passive"))
      (node (ref "U1") (pin "7") (pinfunction "OUT2_7") (pintype "output"))
    )
    (net (code "48") (name "Net-(U2-+LED)") (class "Default")
      (node (ref "R57") (pin "2") (pinfunction "2_2") (pintype "passive"))
      (node (ref "U2") (pin "2") (pinfunction "+LED_2") (pintype "passive"))
    )
    (net (code "49") (name "Net-(U2-A2)") (class "Default")
      (node (ref "R61") (pin "1") (pinfunction "1_1") (pintype "passive"))
      (node (ref "U2") (pin "5") (pinfunction "A2_5") (pintype "passive"))
      (node (ref "U3") (pin "3") (pinfunction "IN1+_3") (pintype "input"))
    )
    (net (code "50") (name "Net-(U3-IN2+)") (class "Default")
      (node (ref "R59") (pin "1") (pinfunction "1_1") (pintype "passive"))
      (node (ref "U3") (pin "5") (pinfunction "IN2+_5") (pintype "input"))
      (node (ref "U4") (pin "5") (pinfunction "A2_5") (pintype "passive"))
    )
    (net (code "51") (name "Net-(U4-+LED)") (class "Default")
      (node (ref "R58") (pin "2") (pinfunction "2_2") (pintype "passive"))
      (node (ref "U4") (pin "2") (pinfunction "+LED_2") (pintype "passive"))
    )
    (net (code "52") (name "Net-(U5-IN1-)") (class "Default")
      (node (ref "C38") (pin "1") (pinfunction "1_1") (pintype "passive"))
      (node (ref "R76") (pin "1") (pinfunction "1_1") (pintype "passive"))
      (node (ref "U5") (pin "2") (pinfunction "IN1-_2") (pintype "input"))
      (node (ref "U6") (pin "4") (pinfunction "A1_4") (pintype "passive"))
    )
    (net (code "53") (name "Net-(U5-IN2-)") (class "Default")
      (node (ref "C37") (pin "1") (pinfunction "1_1") (pintype "passive"))
      (node (ref "R74") (pin "1") (pinfunction "1_1") (pintype "passive"))
      (node (ref "U5") (pin "6") (pinfunction "IN2-_6") (pintype "input"))
      (node (ref "U8") (pin "4") (pinfunction "A1_4") (pintype "passive"))
    )
    (net (code "54") (name "Net-(U5-OUT1)") (class "Default")
      (node (ref "C38") (pin "2") (pinfunction "2_2") (pintype "passive"))
      (node (ref "R71") (pin "1") (pinfunction "1_1") (pintype "passive"))
      (node (ref "U5") (pin "1") (pinfunction "OUT1_1") (pintype "output"))
    )
    (net (code "55") (name "Net-(U5-OUT2)") (class "Default")
      (node (ref "C37") (pin "2") (pinfunction "2_2") (pintype "passive"))
      (node (ref "R72") (pin "1") (pinfunction "1_1") (pintype "passive"))
      (node (ref "U5") (pin "7") (pinfunction "OUT2_7") (pintype "output"))
    )
    (net (code "56") (name "Net-(U6-+LED)") (class "Default")
      (node (ref "R71") (pin "2") (pinfunction "2_2") (pintype "passive"))
      (node (ref "U6") (pin "2") (pinfunction "+LED_2") (pintype "passive"))
    )
    (net (code "57") (name "Net-(U6-A2)") (class "Default")
      (node (ref "R75") (pin "1") (pinfunction "1_1") (pintype "passive"))
      (node (ref "U6") (pin "5") (pinfunction "A2_5") (pintype "passive"))
      (node (ref "U7") (pin "3") (pinfunction "IN1+_3") (pintype "input"))
    )
    (net (code "58") (name "Net-(U7-IN2+)") (class "Default")
      (node (ref "R73") (pin "1") (pinfunction "1_1") (pintype "passive"))
      (node (ref "U7") (pin "5") (pinfunction "IN2+_5") (pintype "input"))
      (node (ref "U8") (pin "5") (pinfunction "A2_5") (pintype "passive"))
    )
    (net (code "59") (name "Net-(U8-+LED)") (class "Default")
      (node (ref "R72") (pin "2") (pinfunction "2_2") (pintype "passive"))
      (node (ref "U8") (pin "2") (pinfunction "+LED_2") (pintype "passive"))
    )
    (net (code "60") (name "Net-(U9-OUT1)") (class "Default")
      (node (ref "C42") (pin "2") (pinfunction "2_2") (pintype "passive"))
      (node (ref "R77") (pin "1") (pinfunction "1_1") (pintype "passive"))
      (node (ref "U9") (pin "1") (pinfunction "OUT1_1") (pintype "output"))
    )
    (net (code "61") (name "Net-(U9-OUT2)") (class "Default")
      (node (ref "C41") (pin "2") (pinfunction "2_2") (pintype "passive"))
      (node (ref "R78") (pin "1") (pinfunction "1_1") (pintype "passive"))
      (node (ref "U9") (pin "7") (pinfunction "OUT2_7") (pintype "output"))
    )
    (net (code "62") (name "Net-(U10-+LED)") (class "Default")
      (node (ref "R77") (pin "2") (pinfunction "2_2") (pintype "passive"))
      (node (ref "U10") (pin "2") (pinfunction "+LED_2") (pintype "passive"))
    )
    (net (code "63") (name "Net-(U10-A1)") (class "Default")
      (node (ref "C42") (pin "1") (pinfunction "1_1") (pintype "passive"))
      (node (ref "R82") (pin "1") (pinfunction "1_1") (pintype "passive"))
      (node (ref "U10") (pin "4") (pinfunction "A1_4") (pintype "passive"))
      (node (ref "U9") (pin "2") (pinfunction "IN1-_2") (pintype "input"))
    )
    (net (code "64") (name "Net-(U10-A2)") (class "Default")
      (node (ref "R81") (pin "1") (pinfunction "1_1") (pintype "passive"))
      (node (ref "U10") (pin "5") (pinfunction "A2_5") (pintype "passive"))
      (node (ref "U11") (pin "3") (pinfunction "IN1+_3") (pintype "input"))
    )
    (net (code "65") (name "Net-(U11-IN2+)") (class "Default")
      (node (ref "R79") (pin "1") (pinfunction "1_1") (pintype "passive"))
      (node (ref "U11") (pin "5") (pinfunction "IN2+_5") (pintype "input"))
      (node (ref "U13") (pin "5") (pinfunction "A2_5") (pintype "passive"))
    )
    (net (code "66") (name "Net-(U13-+LED)") (class "Default")
      (node (ref "R78") (pin "2") (pinfunction "2_2") (pintype "passive"))
      (node (ref "U13") (pin "2") (pinfunction "+LED_2") (pintype "passive"))
    )
    (net (code "67") (name "Net-(U13-A1)") (class "Default")
      (node (ref "C41") (pin "1") (pinfunction "1_1") (pintype "passive"))
      (node (ref "R80") (pin "1") (pinfunction "1_1") (pintype "passive"))
      (node (ref "U13") (pin "4") (pinfunction "A1_4") (pintype "passive"))
      (node (ref "U9") (pin "6") (pinfunction "IN2-_6") (pintype "input"))
    )
    (net (code "68") (name "Net-(U14-IN1-)") (class "Default")
      (node (ref "C50") (pin "1") (pinfunction "1_1") (pintype "passive"))
      (node (ref "R88") (pin "1") (pinfunction "1_1") (pintype "passive"))
      (node (ref "U14") (pin "2") (pinfunction "IN1-_2") (pintype "input"))
      (node (ref "U15") (pin "4") (pinfunction "A1_4") (pintype "passive"))
    )
    (net (code "69") (name "Net-(U14-IN2-)") (class "Default")
      (node (ref "C45") (pin "1") (pinfunction "1_1") (pintype "passive"))
      (node (ref "R86") (pin "1") (pinfunction "1_1") (pintype "passive"))
      (node (ref "U14") (pin "6") (pinfunction "IN2-_6") (pintype "input"))
      (node (ref "U17") (pin "4") (pinfunction "A1_4") (pintype "passive"))
    )
    (net (code "70") (name "Net-(U14-OUT1)") (class "Default")
      (node (ref "C50") (pin "2") (pinfunction "2_2") (pintype "passive"))
      (node (ref "R83") (pin "1") (pinfunction "1_1") (pintype "passive"))
      (node (ref "U14") (pin "1") (pinfunction "OUT1_1") (pintype "output"))
    )
    (net (code "71") (name "Net-(U14-OUT2)") (class "Default")
      (node (ref "C45") (pin "2") (pinfunction "2_2") (pintype "passive"))
      (node (ref "R84") (pin "1") (pinfunction "1_1") (pintype "passive"))
      (node (ref "U14") (pin "7") (pinfunction "OUT2_7") (pintype "output"))
    )
    (net (code "72") (name "Net-(U15-+LED)") (class "Default")
      (node (ref "R83") (pin "2") (pinfunction "2_2") (pintype "passive"))
      (node (ref "U15") (pin "2") (pinfunction "+LED_2") (pintype "passive"))
    )
    (net (code "73") (name "Net-(U15-A2)") (class "Default")
      (node (ref "R87") (pin "1") (pinfunction "1_1") (pintype "passive"))
      (node (ref "U15") (pin "5") (pinfunction "A2_5") (pintype "passive"))
      (node (ref "U16") (pin "3") (pinfunction "IN1+_3") (pintype "input"))
    )
    (net (code "74") (name "Net-(U16-IN2+)") (class "Default")
      (node (ref "R85") (pin "1") (pinfunction "1_1") (pintype "passive"))
      (node (ref "U16") (pin "5") (pinfunction "IN2+_5") (pintype "input"))
      (node (ref "U17") (pin "5") (pinfunction "A2_5") (pintype "passive"))
    )
    (net (code "75") (name "Net-(U17-+LED)") (class "Default")
      (node (ref "R84") (pin "2") (pinfunction "2_2") (pintype "passive"))
      (node (ref "U17") (pin "2") (pinfunction "+LED_2") (pintype "passive"))
    )
    (net (code "76") (name "unconnected-(IC3-I.C._1-Pad2)") (class "Default")
      (node (ref "IC3") (pin "2") (pinfunction "I.C._1_2") (pintype "passive"))
    )
    (net (code "77") (name "unconnected-(IC3-I.C._2-Pad3)") (class "Default")
      (node (ref "IC3") (pin "3") (pinfunction "I.C._2_3") (pintype "passive"))
    )
    (net (code "78") (name "unconnected-(IC3-I.C._3-Pad4)") (class "Default")
      (node (ref "IC3") (pin "4") (pinfunction "I.C._3_4") (pintype "passive"))
    )
    (net (code "79") (name "unconnected-(IC4-I.C._1-Pad2)") (class "Default")
      (node (ref "IC4") (pin "2") (pinfunction "I.C._1_2") (pintype "passive"))
    )
    (net (code "80") (name "unconnected-(IC4-I.C._2-Pad3)") (class "Default")
      (node (ref "IC4") (pin "3") (pinfunction "I.C._2_3") (pintype "passive"))
    )
    (net (code "81") (name "unconnected-(IC4-I.C._3-Pad4)") (class "Default")
      (node (ref "IC4") (pin "4") (pinfunction "I.C._3_4") (pintype "passive"))
    )
    (net (code "82") (name "unconnected-(IC5-I.C._1-Pad2)") (class "Default")
      (node (ref "IC5") (pin "2") (pinfunction "I.C._1_2") (pintype "passive"))
    )
    (net (code "83") (name "unconnected-(IC5-I.C._2-Pad3)") (class "Default")
      (node (ref "IC5") (pin "3") (pinfunction "I.C._2_3") (pintype "passive"))
    )
    (net (code "84") (name "unconnected-(IC5-I.C._3-Pad4)") (class "Default")
      (node (ref "IC5") (pin "4") (pinfunction "I.C._3_4") (pintype "passive"))
    )
    (net (code "85") (name "unconnected-(IC6-I.C._1-Pad2)") (class "Default")
      (node (ref "IC6") (pin "2") (pinfunction "I.C._1_2") (pintype "passive"))
    )
    (net (code "86") (name "unconnected-(IC6-I.C._2-Pad3)") (class "Default")
      (node (ref "IC6") (pin "3") (pinfunction "I.C._2_3") (pintype "passive"))
    )
    (net (code "87") (name "unconnected-(IC6-I.C._3-Pad4)") (class "Default")
      (node (ref "IC6") (pin "4") (pinfunction "I.C._3_4") (pintype "passive"))
    )
    (net (code "88") (name "unconnected-(IC7-I.C._1-Pad2)") (class "Default")
      (node (ref "IC7") (pin "2") (pinfunction "I.C._1_2") (pintype "passive"))
    )
    (net (code "89") (name "unconnected-(IC7-I.C._2-Pad3)") (class "Default")
      (node (ref "IC7") (pin "3") (pinfunction "I.C._2_3") (pintype "passive"))
    )
    (net (code "90") (name "unconnected-(IC7-I.C._3-Pad4)") (class "Default")
      (node (ref "IC7") (pin "4") (pinfunction "I.C._3_4") (pintype "passive"))
    )
    (net (code "91") (name "unconnected-(IC8-I.C._1-Pad2)") (class "Default")
      (node (ref "IC8") (pin "2") (pinfunction "I.C._1_2") (pintype "passive"))
    )
    (net (code "92") (name "unconnected-(IC8-I.C._2-Pad3)") (class "Default")
      (node (ref "IC8") (pin "3") (pinfunction "I.C._2_3") (pintype "passive"))
    )
    (net (code "93") (name "unconnected-(IC8-I.C._3-Pad4)") (class "Default")
      (node (ref "IC8") (pin "4") (pinfunction "I.C._3_4") (pintype "passive"))
    )
    (net (code "94") (name "unconnected-(IC9-I.C._1-Pad2)") (class "Default")
      (node (ref "IC9") (pin "2") (pinfunction "I.C._1_2") (pintype "passive"))
    )
    (net (code "95") (name "unconnected-(IC9-I.C._2-Pad3)") (class "Default")
      (node (ref "IC9") (pin "3") (pinfunction "I.C._2_3") (pintype "passive"))
    )
    (net (code "96") (name "unconnected-(IC9-I.C._3-Pad4)") (class "Default")
      (node (ref "IC9") (pin "4") (pinfunction "I.C._3_4") (pintype "passive"))
    )
    (net (code "97") (name "unconnected-(IC10-I.C._1-Pad2)") (class "Default")
      (node (ref "IC10") (pin "2") (pinfunction "I.C._1_2") (pintype "passive"))
    )
    (net (code "98") (name "unconnected-(IC10-I.C._2-Pad3)") (class "Default")
      (node (ref "IC10") (pin "3") (pinfunction "I.C._2_3") (pintype "passive"))
    )
    (net (code "99") (name "unconnected-(IC10-I.C._3-Pad4)") (class "Default")
      (node (ref "IC10") (pin "4") (pinfunction "I.C._3_4") (pintype "passive"))
    )
    (net (code "100") (name "unconnected-(S1-N.C.-Pad7)") (class "Default")
      (node (ref "S1") (pin "7") (pinfunction "N.C._7") (pintype "passive"))
    )
    (net (code "101") (name "unconnected-(S2-N.C.-Pad7)") (class "Default")
      (node (ref "S2") (pin "7") (pinfunction "N.C._7") (pintype "passive"))
    )
    (net (code "102") (name "unconnected-(U2-N{slash}C1-Pad7)") (class "Default")
      (node (ref "U2") (pin "7") (pinfunction "N/C1_7") (pintype "passive"))
    )
    (net (code "103") (name "unconnected-(U2-N{slash}C2-Pad8)") (class "Default")
      (node (ref "U2") (pin "8") (pinfunction "N/C2_8") (pintype "passive"))
    )
    (net (code "104") (name "unconnected-(U4-N{slash}C1-Pad7)") (class "Default")
      (node (ref "U4") (pin "7") (pinfunction "N/C1_7") (pintype "passive"))
    )
    (net (code "105") (name "unconnected-(U4-N{slash}C2-Pad8)") (class "Default")
      (node (ref "U4") (pin "8") (pinfunction "N/C2_8") (pintype "passive"))
    )
    (net (code "106") (name "unconnected-(U6-N{slash}C1-Pad7)") (class "Default")
      (node (ref "U6") (pin "7") (pinfunction "N/C1_7") (pintype "passive"))
    )
    (net (code "107") (name "unconnected-(U6-N{slash}C2-Pad8)") (class "Default")
      (node (ref "U6") (pin "8") (pinfunction "N/C2_8") (pintype "passive"))
    )
    (net (code "108") (name "unconnected-(U8-N{slash}C1-Pad7)") (class "Default")
      (node (ref "U8") (pin "7") (pinfunction "N/C1_7") (pintype "passive"))
    )
    (net (code "109") (name "unconnected-(U8-N{slash}C2-Pad8)") (class "Default")
      (node (ref "U8") (pin "8") (pinfunction "N/C2_8") (pintype "passive"))
    )
    (net (code "110") (name "unconnected-(U10-N{slash}C1-Pad7)") (class "Default")
      (node (ref "U10") (pin "7") (pinfunction "N/C1_7") (pintype "passive"))
    )
    (net (code "111") (name "unconnected-(U10-N{slash}C2-Pad8)") (class "Default")
      (node (ref "U10") (pin "8") (pinfunction "N/C2_8") (pintype "passive"))
    )
    (net (code "112") (name "unconnected-(U12-INB1-Pad13)") (class "Default")
      (node (ref "U12") (pin "13") (pinfunction "INB1_13") (pintype "input"))
    )
    (net (code "113") (name "unconnected-(U12-INB2-Pad12)") (class "Default")
      (node (ref "U12") (pin "12") (pinfunction "INB2_12") (pintype "input"))
    )
    (net (code "114") (name "unconnected-(U12-OUTA1-Pad4)") (class "Default")
      (node (ref "U12") (pin "4") (pinfunction "OUTA1_4") (pintype "output"))
    )
    (net (code "115") (name "unconnected-(U12-OUTA2-Pad5)") (class "Default")
      (node (ref "U12") (pin "5") (pinfunction "OUTA2_5") (pintype "output"))
    )
    (net (code "116") (name "unconnected-(U13-N{slash}C1-Pad7)") (class "Default")
      (node (ref "U13") (pin "7") (pinfunction "N/C1_7") (pintype "passive"))
    )
    (net (code "117") (name "unconnected-(U13-N{slash}C2-Pad8)") (class "Default")
      (node (ref "U13") (pin "8") (pinfunction "N/C2_8") (pintype "passive"))
    )
    (net (code "118") (name "unconnected-(U15-N{slash}C1-Pad7)") (class "Default")
      (node (ref "U15") (pin "7") (pinfunction "N/C1_7") (pintype "passive"))
    )
    (net (code "119") (name "unconnected-(U15-N{slash}C2-Pad8)") (class "Default")
      (node (ref "U15") (pin "8") (pinfunction "N/C2_8") (pintype "passive"))
    )
    (net (code "120") (name "unconnected-(U17-N{slash}C1-Pad7)") (class "Default")
      (node (ref "U17") (pin "7") (pinfunction "N/C1_7") (pintype "passive"))
    )
    (net (code "121") (name "unconnected-(U17-N{slash}C2-Pad8)") (class "Default")
      (node (ref "U17") (pin "8") (pinfunction "N/C2_8") (pintype "passive"))
    )
  )
)
